# NerdKit.net
KiCad netlist of a schematic drawn in EAGLE
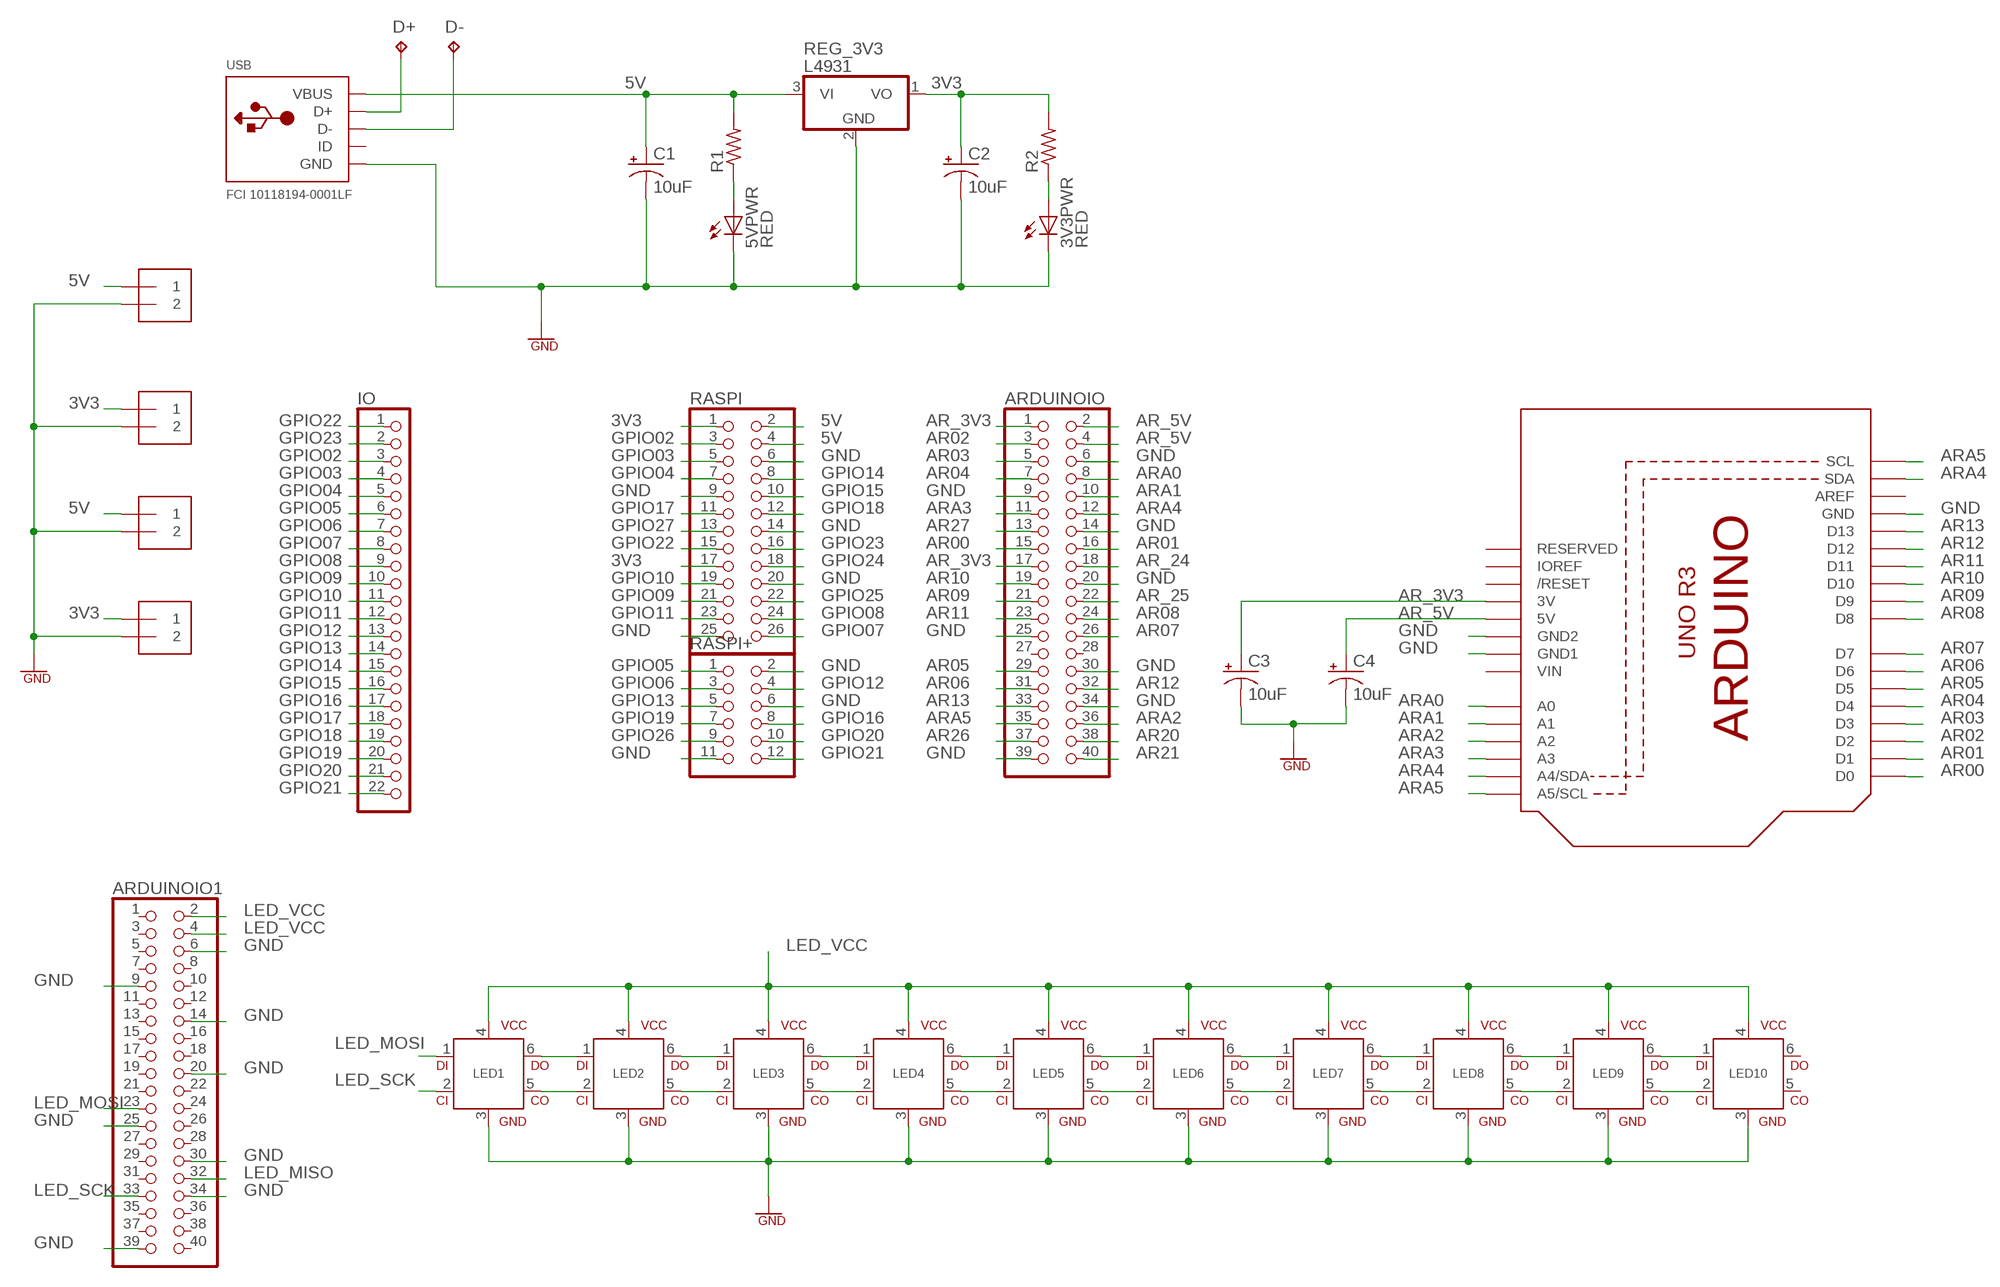
[diagram p0: schematic, sheet 1]

(export (version "E")
  (design (tool "Eeschema 10.0.6"))
  (components
    (comp (ref "3V3PWR")
      (value "RED")
      (footprint "eagle-import:LED3MM")
      (libsource (lib "eagle-import") (part "LED3MM"))
    )
    (comp (ref "5VPWR")
      (value "RED")
      (footprint "eagle-import:LED3MM")
      (libsource (lib "eagle-import") (part "LED3MM"))
    )
    (comp (ref "ARDUINOIO")
      (value "PINHD-2X20")
      (footprint "eagle-import:2X20")
      (libsource (lib "eagle-import") (part "PINHD-2X20"))
    )
    (comp (ref "ARDUINOIO1")
      (value "PINHD-2X20")
      (footprint "eagle-import:2X20")
      (libsource (lib "eagle-import") (part "PINHD-2X20"))
    )
    (comp (ref "C1")
      (value "10uF")
      (footprint "eagle-import:E1,8-4")
      (libsource (lib "eagle-import") (part "CPOL-USE1.8-4"))
    )
    (comp (ref "C2")
      (value "10uF")
      (footprint "eagle-import:E1,8-4")
      (libsource (lib "eagle-import") (part "CPOL-USE1.8-4"))
    )
    (comp (ref "C3")
      (value "10uF")
      (footprint "eagle-import:E1,8-4")
      (libsource (lib "eagle-import") (part "CPOL-USE1.8-4"))
    )
    (comp (ref "C4")
      (value "10uF")
      (footprint "eagle-import:E1,8-4")
      (libsource (lib "eagle-import") (part "CPOL-USE1.8-4"))
    )
    (comp (ref "D+")
      (value "TPPAD1-13")
      (footprint "eagle-import:P1-13")
      (libsource (lib "eagle-import") (part "TPPAD1-13"))
    )
    (comp (ref "D-")
      (value "TPPAD1-13")
      (footprint "eagle-import:P1-13")
      (libsource (lib "eagle-import") (part "TPPAD1-13"))
    )
    (comp (ref "IO")
      (value "PINHD-1X22")
      (footprint "eagle-import:1X22")
      (libsource (lib "eagle-import") (part "PINHD-1X22"))
    )
    (comp (ref "LED1")
      (value "RGBLED5050")
      (footprint "eagle-import:RGBLED5050")
      (libsource (lib "eagle-import") (part "RGBLED5050"))
    )
    (comp (ref "LED2")
      (value "RGBLED5050")
      (footprint "eagle-import:RGBLED5050")
      (libsource (lib "eagle-import") (part "RGBLED5050"))
    )
    (comp (ref "LED3")
      (value "RGBLED5050")
      (footprint "eagle-import:RGBLED5050")
      (libsource (lib "eagle-import") (part "RGBLED5050"))
    )
    (comp (ref "LED4")
      (value "RGBLED5050")
      (footprint "eagle-import:RGBLED5050")
      (libsource (lib "eagle-import") (part "RGBLED5050"))
    )
    (comp (ref "LED5")
      (value "RGBLED5050")
      (footprint "eagle-import:RGBLED5050")
      (libsource (lib "eagle-import") (part "RGBLED5050"))
    )
    (comp (ref "LED6")
      (value "RGBLED5050")
      (footprint "eagle-import:RGBLED5050")
      (libsource (lib "eagle-import") (part "RGBLED5050"))
    )
    (comp (ref "LED7")
      (value "RGBLED5050")
      (footprint "eagle-import:RGBLED5050")
      (libsource (lib "eagle-import") (part "RGBLED5050"))
    )
    (comp (ref "LED8")
      (value "RGBLED5050")
      (footprint "eagle-import:RGBLED5050")
      (libsource (lib "eagle-import") (part "RGBLED5050"))
    )
    (comp (ref "LED9")
      (value "RGBLED5050")
      (footprint "eagle-import:RGBLED5050")
      (libsource (lib "eagle-import") (part "RGBLED5050"))
    )
    (comp (ref "LED10")
      (value "RGBLED5050")
      (footprint "eagle-import:RGBLED5050")
      (libsource (lib "eagle-import") (part "RGBLED5050"))
    )
    (comp (ref "PB1_TB_3V3")
      (value "1X2-3.5MM")
      (footprint "eagle-import:1X2-3.5MM")
      (libsource (lib "eagle-import") (part "1X2-3.5MM"))
    )
    (comp (ref "PB1_TB_5V")
      (value "1X2-3.5MM")
      (footprint "eagle-import:1X2-3.5MM")
      (libsource (lib "eagle-import") (part "1X2-3.5MM"))
    )
    (comp (ref "PB2_TB_3V3")
      (value "1X2-3.5MM")
      (footprint "eagle-import:1X2-3.5MM")
      (libsource (lib "eagle-import") (part "1X2-3.5MM"))
    )
    (comp (ref "PB2_TB_5V")
      (value "1X2-3.5MM")
      (footprint "eagle-import:1X2-3.5MM")
      (libsource (lib "eagle-import") (part "1X2-3.5MM"))
    )
    (comp (ref "R1")
      (value "R-US_0207/7")
      (footprint "eagle-import:0207_7")
      (libsource (lib "eagle-import") (part "R-US_0207/7"))
    )
    (comp (ref "R2")
      (value "R-US_0207/7")
      (footprint "eagle-import:0207_7")
      (libsource (lib "eagle-import") (part "R-US_0207/7"))
    )
    (comp (ref "RASPI")
      (value "PINHD-2X13")
      (footprint "eagle-import:2X13")
      (libsource (lib "eagle-import") (part "PINHD-2X13"))
    )
    (comp (ref "RASPI+")
      (value "PINHD-2X6")
      (footprint "eagle-import:2X06")
      (libsource (lib "eagle-import") (part "PINHD-2X6"))
    )
    (comp (ref "REG_3V3")
      (value "L4931")
      (footprint "eagle-import:TO92")
      (libsource (lib "eagle-import") (part "78L08"))
    )
    (comp (ref "U2")
      (value "ARDUINOR3-PINSONLY")
      (footprint "eagle-import:ARDUINOR3_PINSONLY")
      (libsource (lib "eagle-import") (part "ARDUINOR3-PINSONLY"))
    )
    (comp (ref "USB")
      (value "FCI 10118194-0001LF")
      (footprint "eagle-import:4UCONN_20329")
      (libsource (lib "eagle-import") (part "USBMICRO_20329"))
    )
  )
  (nets
    (net (code "1") (name "/3V3") (class "Default")
      (node (ref "C2") (pin "+") (pinfunction "+_+") (pintype "passive"))
      (node (ref "PB1_TB_3V3") (pin "1") (pinfunction "1_1") (pintype "passive"))
      (node (ref "PB2_TB_3V3") (pin "1") (pinfunction "1_1") (pintype "passive"))
      (node (ref "R2") (pin "2") (pinfunction "2_2") (pintype "passive"))
      (node (ref "RASPI") (pin "1") (pinfunction "1_1") (pintype "passive"))
      (node (ref "RASPI") (pin "17") (pinfunction "17_17") (pintype "passive"))
      (node (ref "REG_3V3") (pin "1") (pinfunction "VO_1") (pintype "passive"))
    )
    (net (code "2") (name "/5V") (class "Default")
      (node (ref "C1") (pin "+") (pinfunction "+_+") (pintype "passive"))
      (node (ref "PB1_TB_5V") (pin "1") (pinfunction "1_1") (pintype "passive"))
      (node (ref "PB2_TB_5V") (pin "1") (pinfunction "1_1") (pintype "passive"))
      (node (ref "R1") (pin "2") (pinfunction "2_2") (pintype "passive"))
      (node (ref "RASPI") (pin "2") (pinfunction "2_2") (pintype "passive"))
      (node (ref "RASPI") (pin "4") (pinfunction "4_4") (pintype "passive"))
      (node (ref "REG_3V3") (pin "3") (pinfunction "VI_3") (pintype "input"))
      (node (ref "USB") (pin "VBUS") (pinfunction "VBUS_VBUS") (pintype "power_in"))
    )
    (net (code "3") (name "/AR00") (class "Default")
      (node (ref "ARDUINOIO") (pin "15") (pinfunction "15_15") (pintype "passive"))
      (node (ref "U2") (pin "D0") (pinfunction "D0_D0") (pintype "bidirectional"))
    )
    (net (code "4") (name "/AR01") (class "Default")
      (node (ref "ARDUINOIO") (pin "16") (pinfunction "16_16") (pintype "passive"))
      (node (ref "U2") (pin "D1") (pinfunction "D1_D1") (pintype "bidirectional"))
    )
    (net (code "5") (name "/AR02") (class "Default")
      (node (ref "ARDUINOIO") (pin "3") (pinfunction "3_3") (pintype "passive"))
      (node (ref "U2") (pin "D2") (pinfunction "D2_D2") (pintype "bidirectional"))
    )
    (net (code "6") (name "/AR03") (class "Default")
      (node (ref "ARDUINOIO") (pin "5") (pinfunction "5_5") (pintype "passive"))
      (node (ref "U2") (pin "D3") (pinfunction "D3_D3") (pintype "bidirectional"))
    )
    (net (code "7") (name "/AR04") (class "Default")
      (node (ref "ARDUINOIO") (pin "7") (pinfunction "7_7") (pintype "passive"))
      (node (ref "U2") (pin "D4") (pinfunction "D4_D4") (pintype "bidirectional"))
    )
    (net (code "8") (name "/AR05") (class "Default")
      (node (ref "ARDUINOIO") (pin "29") (pinfunction "29_29") (pintype "passive"))
      (node (ref "U2") (pin "D5") (pinfunction "D5_D5") (pintype "bidirectional"))
    )
    (net (code "9") (name "/AR06") (class "Default")
      (node (ref "ARDUINOIO") (pin "31") (pinfunction "31_31") (pintype "passive"))
      (node (ref "U2") (pin "D6") (pinfunction "D6_D6") (pintype "bidirectional"))
    )
    (net (code "10") (name "/AR07") (class "Default")
      (node (ref "ARDUINOIO") (pin "26") (pinfunction "26_26") (pintype "passive"))
      (node (ref "U2") (pin "D7") (pinfunction "D7_D7") (pintype "bidirectional"))
    )
    (net (code "11") (name "/AR08") (class "Default")
      (node (ref "ARDUINOIO") (pin "24") (pinfunction "24_24") (pintype "passive"))
      (node (ref "U2") (pin "D8") (pinfunction "D8_D8") (pintype "bidirectional"))
    )
    (net (code "12") (name "/AR09") (class "Default")
      (node (ref "ARDUINOIO") (pin "21") (pinfunction "21_21") (pintype "passive"))
      (node (ref "U2") (pin "D9") (pinfunction "D9_D9") (pintype "bidirectional"))
    )
    (net (code "13") (name "/AR10") (class "Default")
      (node (ref "ARDUINOIO") (pin "19") (pinfunction "19_19") (pintype "passive"))
      (node (ref "U2") (pin "D10") (pinfunction "D10_D10") (pintype "bidirectional"))
    )
    (net (code "14") (name "/AR11") (class "Default")
      (node (ref "ARDUINOIO") (pin "23") (pinfunction "23_23") (pintype "passive"))
      (node (ref "U2") (pin "D11") (pinfunction "D11_D11") (pintype "bidirectional"))
    )
    (net (code "15") (name "/AR12") (class "Default")
      (node (ref "ARDUINOIO") (pin "32") (pinfunction "32_32") (pintype "passive"))
      (node (ref "U2") (pin "D12") (pinfunction "D12_D12") (pintype "bidirectional"))
    )
    (net (code "16") (name "/AR13") (class "Default")
      (node (ref "ARDUINOIO") (pin "33") (pinfunction "33_33") (pintype "passive"))
      (node (ref "U2") (pin "D13") (pinfunction "D13_D13") (pintype "bidirectional"))
    )
    (net (code "17") (name "/AR20") (class "Default")
      (node (ref "ARDUINOIO") (pin "38") (pinfunction "38_38") (pintype "passive"))
    )
    (net (code "18") (name "/AR21") (class "Default")
      (node (ref "ARDUINOIO") (pin "40") (pinfunction "40_40") (pintype "passive"))
    )
    (net (code "19") (name "/AR26") (class "Default")
      (node (ref "ARDUINOIO") (pin "37") (pinfunction "37_37") (pintype "passive"))
    )
    (net (code "20") (name "/AR27") (class "Default")
      (node (ref "ARDUINOIO") (pin "13") (pinfunction "13_13") (pintype "passive"))
    )
    (net (code "21") (name "/ARA0") (class "Default")
      (node (ref "ARDUINOIO") (pin "8") (pinfunction "8_8") (pintype "passive"))
      (node (ref "U2") (pin "A0") (pinfunction "A0_A0") (pintype "bidirectional"))
    )
    (net (code "22") (name "/ARA1") (class "Default")
      (node (ref "ARDUINOIO") (pin "10") (pinfunction "10_10") (pintype "passive"))
      (node (ref "U2") (pin "A1") (pinfunction "A1_A1") (pintype "bidirectional"))
    )
    (net (code "23") (name "/ARA2") (class "Default")
      (node (ref "ARDUINOIO") (pin "36") (pinfunction "36_36") (pintype "passive"))
      (node (ref "U2") (pin "A2") (pinfunction "A2_A2") (pintype "bidirectional"))
    )
    (net (code "24") (name "/ARA3") (class "Default")
      (node (ref "ARDUINOIO") (pin "11") (pinfunction "11_11") (pintype "passive"))
      (node (ref "U2") (pin "A3") (pinfunction "A3_A3") (pintype "bidirectional"))
    )
    (net (code "25") (name "/ARA4") (class "Default")
      (node (ref "ARDUINOIO") (pin "12") (pinfunction "12_12") (pintype "passive"))
      (node (ref "U2") (pin "A4") (pinfunction "A4/SDA_A4") (pintype "bidirectional"))
      (node (ref "U2") (pin "SDA") (pinfunction "SDA_SDA") (pintype "bidirectional"))
    )
    (net (code "26") (name "/ARA5") (class "Default")
      (node (ref "ARDUINOIO") (pin "35") (pinfunction "35_35") (pintype "passive"))
      (node (ref "U2") (pin "A5") (pinfunction "A5/SCL_A5") (pintype "bidirectional"))
      (node (ref "U2") (pin "SCL") (pinfunction "SCL_SCL") (pintype "bidirectional"))
    )
    (net (code "27") (name "/AR_3V3") (class "Default")
      (node (ref "ARDUINOIO") (pin "1") (pinfunction "1_1") (pintype "passive"))
      (node (ref "ARDUINOIO") (pin "17") (pinfunction "17_17") (pintype "passive"))
      (node (ref "C3") (pin "+") (pinfunction "+_+") (pintype "passive"))
      (node (ref "U2") (pin "3V") (pinfunction "3V_3V") (pintype "power_in"))
    )
    (net (code "28") (name "/AR_5V") (class "Default")
      (node (ref "ARDUINOIO") (pin "2") (pinfunction "2_2") (pintype "passive"))
      (node (ref "ARDUINOIO") (pin "4") (pinfunction "4_4") (pintype "passive"))
      (node (ref "C4") (pin "+") (pinfunction "+_+") (pintype "passive"))
      (node (ref "U2") (pin "5V") (pinfunction "5V_5V") (pintype "power_in"))
    )
    (net (code "29") (name "/AR_24") (class "Default")
      (node (ref "ARDUINOIO") (pin "18") (pinfunction "18_18") (pintype "passive"))
    )
    (net (code "30") (name "/AR_25") (class "Default")
      (node (ref "ARDUINOIO") (pin "22") (pinfunction "22_22") (pintype "passive"))
    )
    (net (code "31") (name "/GPIO02") (class "Default")
      (node (ref "IO") (pin "3") (pinfunction "3_3") (pintype "passive"))
      (node (ref "RASPI") (pin "3") (pinfunction "3_3") (pintype "passive"))
    )
    (net (code "32") (name "/GPIO03") (class "Default")
      (node (ref "IO") (pin "4") (pinfunction "4_4") (pintype "passive"))
      (node (ref "RASPI") (pin "5") (pinfunction "5_5") (pintype "passive"))
    )
    (net (code "33") (name "/GPIO04") (class "Default")
      (node (ref "IO") (pin "5") (pinfunction "5_5") (pintype "passive"))
      (node (ref "RASPI") (pin "7") (pinfunction "7_7") (pintype "passive"))
    )
    (net (code "34") (name "/GPIO05") (class "Default")
      (node (ref "IO") (pin "6") (pinfunction "6_6") (pintype "passive"))
      (node (ref "RASPI+") (pin "1") (pinfunction "1_1") (pintype "passive"))
    )
    (net (code "35") (name "/GPIO06") (class "Default")
      (node (ref "IO") (pin "7") (pinfunction "7_7") (pintype "passive"))
      (node (ref "RASPI+") (pin "3") (pinfunction "3_3") (pintype "passive"))
    )
    (net (code "36") (name "/GPIO07") (class "Default")
      (node (ref "IO") (pin "8") (pinfunction "8_8") (pintype "passive"))
      (node (ref "RASPI") (pin "26") (pinfunction "26_26") (pintype "passive"))
    )
    (net (code "37") (name "/GPIO08") (class "Default")
      (node (ref "IO") (pin "9") (pinfunction "9_9") (pintype "passive"))
      (node (ref "RASPI") (pin "24") (pinfunction "24_24") (pintype "passive"))
    )
    (net (code "38") (name "/GPIO09") (class "Default")
      (node (ref "IO") (pin "10") (pinfunction "10_10") (pintype "passive"))
      (node (ref "RASPI") (pin "21") (pinfunction "21_21") (pintype "passive"))
    )
    (net (code "39") (name "/GPIO10") (class "Default")
      (node (ref "IO") (pin "11") (pinfunction "11_11") (pintype "passive"))
      (node (ref "RASPI") (pin "19") (pinfunction "19_19") (pintype "passive"))
    )
    (net (code "40") (name "/GPIO11") (class "Default")
      (node (ref "IO") (pin "12") (pinfunction "12_12") (pintype "passive"))
      (node (ref "RASPI") (pin "23") (pinfunction "23_23") (pintype "passive"))
    )
    (net (code "41") (name "/GPIO12") (class "Default")
      (node (ref "IO") (pin "13") (pinfunction "13_13") (pintype "passive"))
      (node (ref "RASPI+") (pin "4") (pinfunction "4_4") (pintype "passive"))
    )
    (net (code "42") (name "/GPIO13") (class "Default")
      (node (ref "IO") (pin "14") (pinfunction "14_14") (pintype "passive"))
      (node (ref "RASPI+") (pin "5") (pinfunction "5_5") (pintype "passive"))
    )
    (net (code "43") (name "/GPIO14") (class "Default")
      (node (ref "IO") (pin "15") (pinfunction "15_15") (pintype "passive"))
      (node (ref "RASPI") (pin "8") (pinfunction "8_8") (pintype "passive"))
    )
    (net (code "44") (name "/GPIO15") (class "Default")
      (node (ref "IO") (pin "16") (pinfunction "16_16") (pintype "passive"))
      (node (ref "RASPI") (pin "10") (pinfunction "10_10") (pintype "passive"))
    )
    (net (code "45") (name "/GPIO16") (class "Default")
      (node (ref "IO") (pin "17") (pinfunction "17_17") (pintype "passive"))
      (node (ref "RASPI+") (pin "8") (pinfunction "8_8") (pintype "passive"))
    )
    (net (code "46") (name "/GPIO17") (class "Default")
      (node (ref "IO") (pin "18") (pinfunction "18_18") (pintype "passive"))
      (node (ref "RASPI") (pin "11") (pinfunction "11_11") (pintype "passive"))
    )
    (net (code "47") (name "/GPIO18") (class "Default")
      (node (ref "IO") (pin "19") (pinfunction "19_19") (pintype "passive"))
      (node (ref "RASPI") (pin "12") (pinfunction "12_12") (pintype "passive"))
    )
    (net (code "48") (name "/GPIO19") (class "Default")
      (node (ref "IO") (pin "20") (pinfunction "20_20") (pintype "passive"))
      (node (ref "RASPI+") (pin "7") (pinfunction "7_7") (pintype "passive"))
    )
    (net (code "49") (name "/GPIO20") (class "Default")
      (node (ref "IO") (pin "21") (pinfunction "21_21") (pintype "passive"))
      (node (ref "RASPI+") (pin "10") (pinfunction "10_10") (pintype "passive"))
    )
    (net (code "50") (name "/GPIO21") (class "Default")
      (node (ref "IO") (pin "22") (pinfunction "22_22") (pintype "passive"))
      (node (ref "RASPI+") (pin "12") (pinfunction "12_12") (pintype "passive"))
    )
    (net (code "51") (name "/GPIO22") (class "Default")
      (node (ref "IO") (pin "1") (pinfunction "1_1") (pintype "passive"))
      (node (ref "RASPI") (pin "15") (pinfunction "15_15") (pintype "passive"))
    )
    (net (code "52") (name "/GPIO23") (class "Default")
      (node (ref "IO") (pin "2") (pinfunction "2_2") (pintype "passive"))
      (node (ref "RASPI") (pin "16") (pinfunction "16_16") (pintype "passive"))
    )
    (net (code "53") (name "/GPIO24") (class "Default")
      (node (ref "RASPI") (pin "18") (pinfunction "18_18") (pintype "passive"))
    )
    (net (code "54") (name "/GPIO25") (class "Default")
      (node (ref "RASPI") (pin "22") (pinfunction "22_22") (pintype "passive"))
    )
    (net (code "55") (name "/GPIO26") (class "Default")
      (node (ref "RASPI+") (pin "9") (pinfunction "9_9") (pintype "passive"))
    )
    (net (code "56") (name "/GPIO27") (class "Default")
      (node (ref "RASPI") (pin "13") (pinfunction "13_13") (pintype "passive"))
    )
    (net (code "57") (name "/LED_MISO") (class "Default")
      (node (ref "ARDUINOIO1") (pin "32") (pinfunction "32_32") (pintype "passive"))
    )
    (net (code "58") (name "/LED_MOSI") (class "Default")
      (node (ref "ARDUINOIO1") (pin "23") (pinfunction "23_23") (pintype "passive"))
      (node (ref "LED1") (pin "1") (pinfunction "DI_1") (pintype "input"))
    )
    (net (code "59") (name "/LED_SCK") (class "Default")
      (node (ref "ARDUINOIO1") (pin "33") (pinfunction "33_33") (pintype "passive"))
      (node (ref "LED1") (pin "2") (pinfunction "CI_2") (pintype "input"))
    )
    (net (code "60") (name "/LED_VCC") (class "Default")
      (node (ref "ARDUINOIO1") (pin "2") (pinfunction "2_2") (pintype "passive"))
      (node (ref "ARDUINOIO1") (pin "4") (pinfunction "4_4") (pintype "passive"))
      (node (ref "LED1") (pin "4") (pinfunction "VCC_4") (pintype "power_in"))
      (node (ref "LED10") (pin "4") (pinfunction "VCC_4") (pintype "power_in"))
      (node (ref "LED2") (pin "4") (pinfunction "VCC_4") (pintype "power_in"))
      (node (ref "LED3") (pin "4") (pinfunction "VCC_4") (pintype "power_in"))
      (node (ref "LED4") (pin "4") (pinfunction "VCC_4") (pintype "power_in"))
      (node (ref "LED5") (pin "4") (pinfunction "VCC_4") (pintype "power_in"))
      (node (ref "LED6") (pin "4") (pinfunction "VCC_4") (pintype "power_in"))
      (node (ref "LED7") (pin "4") (pinfunction "VCC_4") (pintype "power_in"))
      (node (ref "LED8") (pin "4") (pinfunction "VCC_4") (pintype "power_in"))
      (node (ref "LED9") (pin "4") (pinfunction "VCC_4") (pintype "power_in"))
    )
    (net (code "61") (name "/VIN") (class "Default")
      (node (ref "U2") (pin "VIN") (pinfunction "VIN_VIN") (pintype "power_in"))
    )
    (net (code "62") (name "GND") (class "Default")
      (node (ref "3V3PWR") (pin "K") (pinfunction "C_K") (pintype "passive"))
      (node (ref "5VPWR") (pin "K") (pinfunction "C_K") (pintype "passive"))
      (node (ref "ARDUINOIO") (pin "14") (pinfunction "14_14") (pintype "passive"))
      (node (ref "ARDUINOIO") (pin "20") (pinfunction "20_20") (pintype "passive"))
      (node (ref "ARDUINOIO") (pin "25") (pinfunction "25_25") (pintype "passive"))
      (node (ref "ARDUINOIO") (pin "30") (pinfunction "30_30") (pintype "passive"))
      (node (ref "ARDUINOIO") (pin "34") (pinfunction "34_34") (pintype "passive"))
      (node (ref "ARDUINOIO") (pin "39") (pinfunction "39_39") (pintype "passive"))
      (node (ref "ARDUINOIO") (pin "6") (pinfunction "6_6") (pintype "passive"))
      (node (ref "ARDUINOIO") (pin "9") (pinfunction "9_9") (pintype "passive"))
      (node (ref "ARDUINOIO1") (pin "14") (pinfunction "14_14") (pintype "passive"))
      (node (ref "ARDUINOIO1") (pin "20") (pinfunction "20_20") (pintype "passive"))
      (node (ref "ARDUINOIO1") (pin "25") (pinfunction "25_25") (pintype "passive"))
      (node (ref "ARDUINOIO1") (pin "30") (pinfunction "30_30") (pintype "passive"))
      (node (ref "ARDUINOIO1") (pin "34") (pinfunction "34_34") (pintype "passive"))
      (node (ref "ARDUINOIO1") (pin "39") (pinfunction "39_39") (pintype "passive"))
      (node (ref "ARDUINOIO1") (pin "6") (pinfunction "6_6") (pintype "passive"))
      (node (ref "ARDUINOIO1") (pin "9") (pinfunction "9_9") (pintype "passive"))
      (node (ref "C1") (pin "-") (pinfunction "-_-") (pintype "passive"))
      (node (ref "C2") (pin "-") (pinfunction "-_-") (pintype "passive"))
      (node (ref "C3") (pin "-") (pinfunction "-_-") (pintype "passive"))
      (node (ref "C4") (pin "-") (pinfunction "-_-") (pintype "passive"))
      (node (ref "LED1") (pin "3") (pinfunction "GND_3") (pintype "power_in"))
      (node (ref "LED10") (pin "3") (pinfunction "GND_3") (pintype "power_in"))
      (node (ref "LED2") (pin "3") (pinfunction "GND_3") (pintype "power_in"))
      (node (ref "LED3") (pin "3") (pinfunction "GND_3") (pintype "power_in"))
      (node (ref "LED4") (pin "3") (pinfunction "GND_3") (pintype "power_in"))
      (node (ref "LED5") (pin "3") (pinfunction "GND_3") (pintype "power_in"))
      (node (ref "LED6") (pin "3") (pinfunction "GND_3") (pintype "power_in"))
      (node (ref "LED7") (pin "3") (pinfunction "GND_3") (pintype "power_in"))
      (node (ref "LED8") (pin "3") (pinfunction "GND_3") (pintype "power_in"))
      (node (ref "LED9") (pin "3") (pinfunction "GND_3") (pintype "power_in"))
      (node (ref "PB1_TB_3V3") (pin "2") (pinfunction "2_2") (pintype "passive"))
      (node (ref "PB1_TB_5V") (pin "2") (pinfunction "2_2") (pintype "passive"))
      (node (ref "PB2_TB_3V3") (pin "2") (pinfunction "2_2") (pintype "passive"))
      (node (ref "PB2_TB_5V") (pin "2") (pinfunction "2_2") (pintype "passive"))
      (node (ref "RASPI") (pin "14") (pinfunction "14_14") (pintype "passive"))
      (node (ref "RASPI") (pin "20") (pinfunction "20_20") (pintype "passive"))
      (node (ref "RASPI") (pin "25") (pinfunction "25_25") (pintype "passive"))
      (node (ref "RASPI") (pin "6") (pinfunction "6_6") (pintype "passive"))
      (node (ref "RASPI") (pin "9") (pinfunction "9_9") (pintype "passive"))
      (node (ref "RASPI+") (pin "11") (pinfunction "11_11") (pintype "passive"))
      (node (ref "RASPI+") (pin "2") (pinfunction "2_2") (pintype "passive"))
      (node (ref "RASPI+") (pin "6") (pinfunction "6_6") (pintype "passive"))
      (node (ref "REG_3V3") (pin "2") (pinfunction "GND_2") (pintype "passive"))
      (node (ref "U2") (pin "GND") (pinfunction "GND_GND") (pintype "power_in"))
      (node (ref "U2") (pin "GND1") (pinfunction "GND1_GND1") (pintype "power_in"))
      (node (ref "U2") (pin "GND2") (pinfunction "GND2_GND2") (pintype "power_in"))
      (node (ref "USB") (pin "BASE@1") (pinfunction "GND_BASE@1") (pintype "power_in"))
      (node (ref "USB") (pin "BASE@2") (pinfunction "GND_BASE@2") (pintype "power_in"))
      (node (ref "USB") (pin "GND") (pinfunction "GND_GND") (pintype "power_in"))
      (node (ref "USB") (pin "SPRT@1") (pinfunction "GND_SPRT@1") (pintype "power_in"))
      (node (ref "USB") (pin "SPRT@2") (pinfunction "GND_SPRT@2") (pintype "power_in"))
      (node (ref "USB") (pin "SPRT@3") (pinfunction "GND_SPRT@3") (pintype "power_in"))
      (node (ref "USB") (pin "SPRT@4") (pinfunction "GND_SPRT@4") (pintype "power_in"))
    )
    (net (code "63") (name "Net-(3V3PWR-PadA)") (class "Default")
      (node (ref "3V3PWR") (pin "A") (pinfunction "A_A") (pintype "passive"))
      (node (ref "R2") (pin "1") (pinfunction "1_1") (pintype "passive"))
    )
    (net (code "64") (name "Net-(5VPWR-PadA)") (class "Default")
      (node (ref "5VPWR") (pin "A") (pinfunction "A_A") (pintype "passive"))
      (node (ref "R1") (pin "1") (pinfunction "1_1") (pintype "passive"))
    )
    (net (code "65") (name "Net-(D+-PadTP)") (class "Default")
      (node (ref "D+") (pin "TP") (pinfunction "TP_TP") (pintype "input"))
      (node (ref "USB") (pin "D+") (pinfunction "D+_D+") (pintype "bidirectional"))
    )
    (net (code "66") (name "Net-(D--PadTP)") (class "Default")
      (node (ref "D-") (pin "TP") (pinfunction "TP_TP") (pintype "input"))
      (node (ref "USB") (pin "D-") (pinfunction "D-_D-") (pintype "bidirectional"))
    )
    (net (code "67") (name "Net-(LED1-CO)") (class "Default")
      (node (ref "LED1") (pin "5") (pinfunction "CO_5") (pintype "output"))
      (node (ref "LED2") (pin "2") (pinfunction "CI_2") (pintype "input"))
    )
    (net (code "68") (name "Net-(LED1-DO)") (class "Default")
      (node (ref "LED1") (pin "6") (pinfunction "DO_6") (pintype "output"))
      (node (ref "LED2") (pin "1") (pinfunction "DI_1") (pintype "input"))
    )
    (net (code "69") (name "Net-(LED2-CO)") (class "Default")
      (node (ref "LED2") (pin "5") (pinfunction "CO_5") (pintype "output"))
      (node (ref "LED3") (pin "2") (pinfunction "CI_2") (pintype "input"))
    )
    (net (code "70") (name "Net-(LED2-DO)") (class "Default")
      (node (ref "LED2") (pin "6") (pinfunction "DO_6") (pintype "output"))
      (node (ref "LED3") (pin "1") (pinfunction "DI_1") (pintype "input"))
    )
    (net (code "71") (name "Net-(LED3-CO)") (class "Default")
      (node (ref "LED3") (pin "5") (pinfunction "CO_5") (pintype "output"))
      (node (ref "LED4") (pin "2") (pinfunction "CI_2") (pintype "input"))
    )
    (net (code "72") (name "Net-(LED3-DO)") (class "Default")
      (node (ref "LED3") (pin "6") (pinfunction "DO_6") (pintype "output"))
      (node (ref "LED4") (pin "1") (pinfunction "DI_1") (pintype "input"))
    )
    (net (code "73") (name "Net-(LED4-CO)") (class "Default")
      (node (ref "LED4") (pin "5") (pinfunction "CO_5") (pintype "output"))
      (node (ref "LED5") (pin "2") (pinfunction "CI_2") (pintype "input"))
    )
    (net (code "74") (name "Net-(LED4-DO)") (class "Default")
      (node (ref "LED4") (pin "6") (pinfunction "DO_6") (pintype "output"))
      (node (ref "LED5") (pin "1") (pinfunction "DI_1") (pintype "input"))
    )
    (net (code "75") (name "Net-(LED5-CO)") (class "Default")
      (node (ref "LED5") (pin "5") (pinfunction "CO_5") (pintype "output"))
      (node (ref "LED6") (pin "2") (pinfunction "CI_2") (pintype "input"))
    )
    (net (code "76") (name "Net-(LED5-DO)") (class "Default")
      (node (ref "LED5") (pin "6") (pinfunction "DO_6") (pintype "output"))
      (node (ref "LED6") (pin "1") (pinfunction "DI_1") (pintype "input"))
    )
    (net (code "77") (name "Net-(LED6-CO)") (class "Default")
      (node (ref "LED6") (pin "5") (pinfunction "CO_5") (pintype "output"))
      (node (ref "LED7") (pin "2") (pinfunction "CI_2") (pintype "input"))
    )
    (net (code "78") (name "Net-(LED6-DO)") (class "Default")
      (node (ref "LED6") (pin "6") (pinfunction "DO_6") (pintype "output"))
      (node (ref "LED7") (pin "1") (pinfunction "DI_1") (pintype "input"))
    )
    (net (code "79") (name "Net-(LED7-CO)") (class "Default")
      (node (ref "LED7") (pin "5") (pinfunction "CO_5") (pintype "output"))
      (node (ref "LED8") (pin "2") (pinfunction "CI_2") (pintype "input"))
    )
    (net (code "80") (name "Net-(LED7-DO)") (class "Default")
      (node (ref "LED7") (pin "6") (pinfunction "DO_6") (pintype "output"))
      (node (ref "LED8") (pin "1") (pinfunction "DI_1") (pintype "input"))
    )
    (net (code "81") (name "Net-(LED8-CO)") (class "Default")
      (node (ref "LED8") (pin "5") (pinfunction "CO_5") (pintype "output"))
      (node (ref "LED9") (pin "2") (pinfunction "CI_2") (pintype "input"))
    )
    (net (code "82") (name "Net-(LED8-DO)") (class "Default")
      (node (ref "LED8") (pin "6") (pinfunction "DO_6") (pintype "output"))
      (node (ref "LED9") (pin "1") (pinfunction "DI_1") (pintype "input"))
    )
    (net (code "83") (name "Net-(LED10-CI)") (class "Default")
      (node (ref "LED10") (pin "2") (pinfunction "CI_2") (pintype "input"))
      (node (ref "LED9") (pin "5") (pinfunction "CO_5") (pintype "output"))
    )
    (net (code "84") (name "Net-(LED10-DI)") (class "Default")
      (node (ref "LED10") (pin "1") (pinfunction "DI_1") (pintype "input"))
      (node (ref "LED9") (pin "6") (pinfunction "DO_6") (pintype "output"))
    )
    (net (code "85") (name "unconnected-(ARDUINOIO-Pad27)") (class "Default")
      (node (ref "ARDUINOIO") (pin "27") (pinfunction "27_27") (pintype "passive"))
    )
    (net (code "86") (name "unconnected-(ARDUINOIO-Pad28)") (class "Default")
      (node (ref "ARDUINOIO") (pin "28") (pinfunction "28_28") (pintype "passive"))
    )
    (net (code "87") (name "unconnected-(ARDUINOIO1-Pad1)") (class "Default")
      (node (ref "ARDUINOIO1") (pin "1") (pinfunction "1_1") (pintype "passive"))
    )
    (net (code "88") (name "unconnected-(ARDUINOIO1-Pad3)") (class "Default")
      (node (ref "ARDUINOIO1") (pin "3") (pinfunction "3_3") (pintype "passive"))
    )
    (net (code "89") (name "unconnected-(ARDUINOIO1-Pad5)") (class "Default")
      (node (ref "ARDUINOIO1") (pin "5") (pinfunction "5_5") (pintype "passive"))
    )
    (net (code "90") (name "unconnected-(ARDUINOIO1-Pad7)") (class "Default")
      (node (ref "ARDUINOIO1") (pin "7") (pinfunction "7_7") (pintype "passive"))
    )
    (net (code "91") (name "unconnected-(ARDUINOIO1-Pad8)") (class "Default")
      (node (ref "ARDUINOIO1") (pin "8") (pinfunction "8_8") (pintype "passive"))
    )
    (net (code "92") (name "unconnected-(ARDUINOIO1-Pad10)") (class "Default")
      (node (ref "ARDUINOIO1") (pin "10") (pinfunction "10_10") (pintype "passive"))
    )
    (net (code "93") (name "unconnected-(ARDUINOIO1-Pad11)") (class "Default")
      (node (ref "ARDUINOIO1") (pin "11") (pinfunction "11_11") (pintype "passive"))
    )
    (net (code "94") (name "unconnected-(ARDUINOIO1-Pad12)") (class "Default")
      (node (ref "ARDUINOIO1") (pin "12") (pinfunction "12_12") (pintype "passive"))
    )
    (net (code "95") (name "unconnected-(ARDUINOIO1-Pad13)") (class "Default")
      (node (ref "ARDUINOIO1") (pin "13") (pinfunction "13_13") (pintype "passive"))
    )
    (net (code "96") (name "unconnected-(ARDUINOIO1-Pad15)") (class "Default")
      (node (ref "ARDUINOIO1") (pin "15") (pinfunction "15_15") (pintype "passive"))
    )
    (net (code "97") (name "unconnected-(ARDUINOIO1-Pad16)") (class "Default")
      (node (ref "ARDUINOIO1") (pin "16") (pinfunction "16_16") (pintype "passive"))
    )
    (net (code "98") (name "unconnected-(ARDUINOIO1-Pad17)") (class "Default")
      (node (ref "ARDUINOIO1") (pin "17") (pinfunction "17_17") (pintype "passive"))
    )
    (net (code "99") (name "unconnected-(ARDUINOIO1-Pad18)") (class "Default")
      (node (ref "ARDUINOIO1") (pin "18") (pinfunction "18_18") (pintype "passive"))
    )
    (net (code "100") (name "unconnected-(ARDUINOIO1-Pad19)") (class "Default")
      (node (ref "ARDUINOIO1") (pin "19") (pinfunction "19_19") (pintype "passive"))
    )
    (net (code "101") (name "unconnected-(ARDUINOIO1-Pad21)") (class "Default")
      (node (ref "ARDUINOIO1") (pin "21") (pinfunction "21_21") (pintype "passive"))
    )
    (net (code "102") (name "unconnected-(ARDUINOIO1-Pad22)") (class "Default")
      (node (ref "ARDUINOIO1") (pin "22") (pinfunction "22_22") (pintype "passive"))
    )
    (net (code "103") (name "unconnected-(ARDUINOIO1-Pad24)") (class "Default")
      (node (ref "ARDUINOIO1") (pin "24") (pinfunction "24_24") (pintype "passive"))
    )
    (net (code "104") (name "unconnected-(ARDUINOIO1-Pad26)") (class "Default")
      (node (ref "ARDUINOIO1") (pin "26") (pinfunction "26_26") (pintype "passive"))
    )
    (net (code "105") (name "unconnected-(ARDUINOIO1-Pad27)") (class "Default")
      (node (ref "ARDUINOIO1") (pin "27") (pinfunction "27_27") (pintype "passive"))
    )
    (net (code "106") (name "unconnected-(ARDUINOIO1-Pad28)") (class "Default")
      (node (ref "ARDUINOIO1") (pin "28") (pinfunction "28_28") (pintype "passive"))
    )
    (net (code "107") (name "unconnected-(ARDUINOIO1-Pad29)") (class "Default")
      (node (ref "ARDUINOIO1") (pin "29") (pinfunction "29_29") (pintype "passive"))
    )
    (net (code "108") (name "unconnected-(ARDUINOIO1-Pad31)") (class "Default")
      (node (ref "ARDUINOIO1") (pin "31") (pinfunction "31_31") (pintype "passive"))
    )
    (net (code "109") (name "unconnected-(ARDUINOIO1-Pad35)") (class "Default")
      (node (ref "ARDUINOIO1") (pin "35") (pinfunction "35_35") (pintype "passive"))
    )
    (net (code "110") (name "unconnected-(ARDUINOIO1-Pad36)") (class "Default")
      (node (ref "ARDUINOIO1") (pin "36") (pinfunction "36_36") (pintype "passive"))
    )
    (net (code "111") (name "unconnected-(ARDUINOIO1-Pad37)") (class "Default")
      (node (ref "ARDUINOIO1") (pin "37") (pinfunction "37_37") (pintype "passive"))
    )
    (net (code "112") (name "unconnected-(ARDUINOIO1-Pad38)") (class "Default")
      (node (ref "ARDUINOIO1") (pin "38") (pinfunction "38_38") (pintype "passive"))
    )
    (net (code "113") (name "unconnected-(ARDUINOIO1-Pad40)") (class "Default")
      (node (ref "ARDUINOIO1") (pin "40") (pinfunction "40_40") (pintype "passive"))
    )
    (net (code "114") (name "unconnected-(LED10-CO-Pad5)") (class "Default")
      (node (ref "LED10") (pin "5") (pinfunction "CO_5") (pintype "output"))
    )
    (net (code "115") (name "unconnected-(LED10-DO-Pad6)") (class "Default")
      (node (ref "LED10") (pin "6") (pinfunction "DO_6") (pintype "output"))
    )
    (net (code "116") (name "unconnected-(U2-PadAREF)") (class "Default")
      (node (ref "U2") (pin "AREF") (pinfunction "AREF_AREF") (pintype "bidirectional"))
    )
    (net (code "117") (name "unconnected-(U2-PadIOREF)") (class "Default")
      (node (ref "U2") (pin "IOREF") (pinfunction "IOREF_IOREF") (pintype "output"))
    )
    (net (code "118") (name "unconnected-(U2-PadRESERVED)") (class "Default")
      (node (ref "U2") (pin "RESERVED") (pinfunction "RESERVED_RESERVED") (pintype "no_connect"))
    )
    (net (code "119") (name "unconnected-(U2-{slash}RESET-PadRESET)") (class "Default")
      (node (ref "U2") (pin "RESET") (pinfunction "/RESET_RESET") (pintype "bidirectional"))
    )
    (net (code "120") (name "unconnected-(USB-PadID)") (class "Default")
      (node (ref "USB") (pin "ID") (pinfunction "ID_ID") (pintype "bidirectional"))
    )
  )
)
